# Proto_Recepteur.net
KiCad netlist of a schematic drawn in Altium Designer
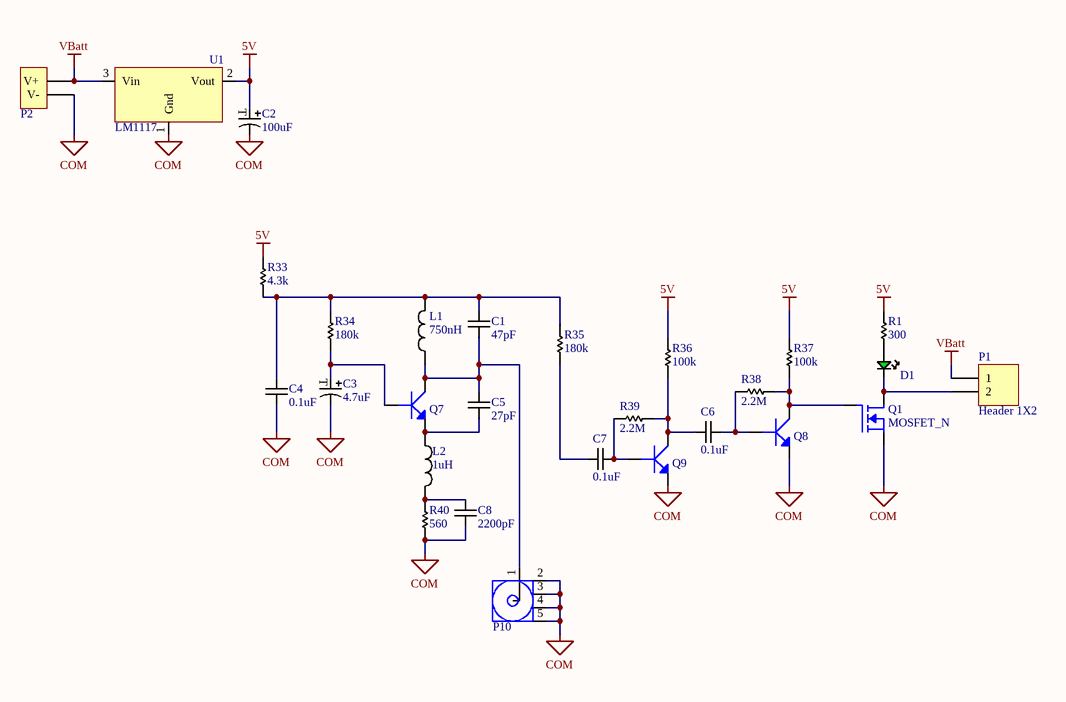
[diagram p0: Proto Recepteur.SchDoc]

(export (version "E")
  (design (tool "Eeschema 10.0.6"))
  (components
    (comp (ref "C1")
      (value "47pF")
      (footprint "0805 - Cap Non-Polarized")
      (description "CAP CER 47PF 100V 5% NP0 0603")
      (fields
        (field (name "PART NUMBER") "Cap-TDK-CGA-47pF-0805")
        (field (name "MANUFACTURER") "TDK")
        (field (name "CREATED BY") "Pier-Yves")
      )
      (libsource (lib "local") (part "Cap"))
    )
    (comp (ref "C2")
      (value "100uF")
      (footprint "Tantalum - Case C")
      (description "CAP TANT 100 16V 10% 2413")
      (fields
        (field (name "PART NUMBER") "Kemet-T491-100uF-16V-1 Ohm")
        (field (name "MANUFACTURER") "Kemet")
        (field (name "CREATED BY") "Frederic")
      )
      (libsource (lib "local") (part "Cap Tantal"))
    )
    (comp (ref "C3")
      (value "4.7uF")
      (footprint "Tantalum - Case D")
      (description "CAP TANT 4.7 35V 10% 2917")
      (fields
        (field (name "PART NUMBER") "Kemet-T491-4.7uF-35V-1.5 Ohm")
        (field (name "MANUFACTURER") "Kemet")
        (field (name "CREATED BY") "Frederic")
      )
      (libsource (lib "local") (part "Cap Tantal"))
    )
    (comp (ref "C4")
      (value "0.1uF")
      (footprint "0805 - Cap Non-Polarized")
      (description "CAP CER 0.1UF 100V 10% X7R 0805")
      (fields
        (field (name "PART NUMBER") "Cap-TDK-CGA-0.1uF-0805")
        (field (name "MANUFACTURER") "TDK")
        (field (name "CREATED BY") "Pier-Yves")
      )
      (libsource (lib "local") (part "Cap"))
    )
    (comp (ref "C5")
      (value "27pF")
      (footprint "0805 - Cap Non-Polarized")
      (description "CAP CER 27PF 50V 5% NP0 0603")
      (fields
        (field (name "PART NUMBER") "Cap-TDK-CGA-27pF-0805")
        (field (name "MANUFACTURER") "TDK")
        (field (name "CREATED BY") "Pier-Yves")
      )
      (libsource (lib "local") (part "Cap"))
    )
    (comp (ref "C6")
      (value "0.1uF")
      (footprint "0805 - Cap Non-Polarized")
      (description "CAP CER 0.1UF 100V 10% X7R 0805")
      (fields
        (field (name "PART NUMBER") "Cap-TDK-CGA-0.1uF-0805")
        (field (name "MANUFACTURER") "TDK")
        (field (name "CREATED BY") "Pier-Yves")
      )
      (libsource (lib "local") (part "Cap"))
    )
    (comp (ref "C7")
      (value "0.1uF")
      (footprint "0805 - Cap Non-Polarized")
      (description "CAP CER 0.1UF 100V 10% X7R 0805")
      (fields
        (field (name "PART NUMBER") "Cap-TDK-CGA-0.1uF-0805")
        (field (name "MANUFACTURER") "TDK")
        (field (name "CREATED BY") "Pier-Yves")
      )
      (libsource (lib "local") (part "Cap"))
    )
    (comp (ref "C8")
      (value "2200pF")
      (footprint "0805 - Cap Non-Polarized")
      (description "CAP CER 2200PF 100V 5% NP0 0805")
      (fields
        (field (name "PART NUMBER") "Cap-TDK-CGA-2200pF-0805")
        (field (name "MANUFACTURER") "TDK")
        (field (name "CREATED BY") "Pier-Yves")
      )
      (libsource (lib "local") (part "Cap"))
    )
    (comp (ref "D1")
      (value "Green")
      (footprint "0805 - Led Green")
      (description "Led Green 0805 Low Brightness - 10mA")
      (fields
        (field (name "PART NUMBER") "LED-Green-lowBrigthness-0805")
        (field (name "MANUFACTURER") "Lite-On inc.")
        (field (name "CREATED BY") "Pier-Yves")
      )
      (libsource (lib "local") (part "Led Green"))
    )
    (comp (ref "L1")
      (value "750nH")
      (footprint "1008 - INDUCTOR")
      (description "IND 750NH 360MA SRF 360MHZ 1008")
      (fields
        (field (name "PART NUMBER") "Murata-LQW2UA-Ind-AirCore-750nH")
        (field (name "MANUFACTURER") "Murata Electronics North America")
        (field (name "CREATED BY") "Frederic")
      )
      (libsource (lib "local") (part "Inductor"))
    )
    (comp (ref "L2")
      (value "1uH")
      (footprint "1008 - INDUCTOR")
      (description "IND 1000NH 370MA SRF 290MHZ 1008")
      (fields
        (field (name "PART NUMBER") "Murata-LQW2UA-Ind-AirCore-1uH")
        (field (name "MANUFACTURER") "Murata Electronics North America")
        (field (name "CREATED BY") "Frederic")
      )
      (libsource (lib "local") (part "Inductor"))
    )
    (comp (ref "P1")
      (value "Header 1X2")
      (footprint "Headers - 1x2 - R/A - Lock")
      (fields
        (field (name "PART NUMBER") "Header-0.100-R/A-Lock-1X2")
        (field (name "MANUFACTURER") "Molex Inc.")
        (field (name "PUBLISHER") "Altium Limited")
        (field (name "CREATED BY") "Pier-Yves")
      )
      (libsource (lib "local") (part "Header 1X2"))
    )
    (comp (ref "P2")
      (value "Battery Holder")
      (footprint "Battery Holder - 9V - THT")
      (description "HOLDER BATTERY 9V PC MOUNT")
      (fields
        (field (name "PART NUMBER") "Battery Holder-9V-THT-Open")
        (field (name "MANUFACTURER") "MPD")
        (field (name "CREATED BY") "Pier-Yves")
      )
      (libsource (lib "local") (part "Battery Holder - 2 pin"))
    )
    (comp (ref "P10")
      (value "Coax-F")
      (footprint "SMA-Female-R/A-THT")
      (description "CONN SMA JACK R/A 50 OHM PCB")
      (fields
        (field (name "PART NUMBER") "coax-sma-ra-tht")
        (field (name "MANUFACTURER") "Linx Technologies Inc.")
        (field (name "CREATED BY") "Pier-Yves")
      )
      (libsource (lib "local") (part "COAX-F"))
    )
    (comp (ref "Q1")
      (value "MOSFET_N")
      (footprint "SOT23-3")
      (description "MosFET Channel-N SOT-23-3 3.3A")
      (fields
        (field (name "PART NUMBER") "2N7002")
        (field (name "MANUFACTURER") "Vishay Siliconix")
        (field (name "CREATED BY") "Pier-Yves")
      )
      (libsource (lib "local") (part "MOSFET_N_GSD"))
    )
    (comp (ref "Q7")
      (value "NPN")
      (footprint "SOT23-3")
      (description "TRANS NPN 40V 350MW SMD SOT23-3")
      (fields
        (field (name "PART NUMBER") "MMBT2222A-7-F")
        (field (name "MANUFACTURER") "Diodes Inc.")
        (field (name "CREATED BY") "Pier-Yves")
      )
      (libsource (lib "local") (part "BJT_NPN_BEC"))
    )
    (comp (ref "Q8")
      (value "NPN")
      (footprint "SOT23-3")
      (description "TRANS NPN 40V 350MW SMD SOT23-3")
      (fields
        (field (name "PART NUMBER") "MMBT2222A-7-F")
        (field (name "MANUFACTURER") "Diodes Inc.")
        (field (name "CREATED BY") "Pier-Yves")
      )
      (libsource (lib "local") (part "BJT_NPN_BEC"))
    )
    (comp (ref "Q9")
      (value "NPN")
      (footprint "SOT23-3")
      (description "TRANS NPN 40V 350MW SMD SOT23-3")
      (fields
        (field (name "PART NUMBER") "MMBT2222A-7-F")
        (field (name "MANUFACTURER") "Diodes Inc.")
        (field (name "CREATED BY") "Pier-Yves")
      )
      (libsource (lib "local") (part "BJT_NPN_BEC"))
    )
    (comp (ref "R1")
      (value "300")
      (footprint "0805 - Resistor")
      (description "RES 300 OHM 1/8W 5% 0805 SMD")
      (fields
        (field (name "PART NUMBER") "Yagao-RC0805-300")
        (field (name "MANUFACTURER") "Yagao")
        (field (name "CREATED BY") "Pier-Yves")
      )
      (libsource (lib "local") (part "Res"))
    )
    (comp (ref "R33")
      (value "4.3k")
      (footprint "0805 - Resistor")
      (description "RES 4.3K OHM 1/8W 5% 0805 SMD")
      (fields
        (field (name "PART NUMBER") "Yagao-RC0805-4.3k")
        (field (name "MANUFACTURER") "Yagao")
        (field (name "CREATED BY") "Pier-Yves")
      )
      (libsource (lib "local") (part "Res"))
    )
    (comp (ref "R34")
      (value "180k")
      (footprint "0805 - Resistor")
      (description "RES 180K OHM 1/8W 5% 0805 SMD")
      (fields
        (field (name "PART NUMBER") "Yagao-RC0805-180k")
        (field (name "MANUFACTURER") "Yagao")
        (field (name "CREATED BY") "Pier-Yves")
      )
      (libsource (lib "local") (part "Res"))
    )
    (comp (ref "R35")
      (value "180k")
      (footprint "0805 - Resistor")
      (description "RES 180K OHM 1/8W 5% 0805 SMD")
      (fields
        (field (name "PART NUMBER") "Yagao-RC0805-180k")
        (field (name "MANUFACTURER") "Yagao")
        (field (name "CREATED BY") "Pier-Yves")
      )
      (libsource (lib "local") (part "Res"))
    )
    (comp (ref "R36")
      (value "100k")
      (footprint "0805 - Resistor")
      (description "RES 100K OHM 1/8W 5% 0805 SMD")
      (fields
        (field (name "PART NUMBER") "Yagao-RC0805-100k")
        (field (name "MANUFACTURER") "Yagao")
        (field (name "CREATED BY") "Pier-Yves")
      )
      (libsource (lib "local") (part "Res"))
    )
    (comp (ref "R37")
      (value "100k")
      (footprint "0805 - Resistor")
      (description "RES 100K OHM 1/8W 5% 0805 SMD")
      (fields
        (field (name "PART NUMBER") "Yagao-RC0805-100k")
        (field (name "MANUFACTURER") "Yagao")
        (field (name "CREATED BY") "Pier-Yves")
      )
      (libsource (lib "local") (part "Res"))
    )
    (comp (ref "R38")
      (value "2.2M")
      (footprint "0805 - Resistor")
      (description "RES 2.2M OHM 1/8W 5% 0805 SMD")
      (fields
        (field (name "PART NUMBER") "Yagao-RC0805-2.2M")
        (field (name "MANUFACTURER") "Yagao")
        (field (name "CREATED BY") "Pier-Yves")
      )
      (libsource (lib "local") (part "Res"))
    )
    (comp (ref "R39")
      (value "2.2M")
      (footprint "0805 - Resistor")
      (description "RES 2.2M OHM 1/8W 5% 0805 SMD")
      (fields
        (field (name "PART NUMBER") "Yagao-RC0805-2.2M")
        (field (name "MANUFACTURER") "Yagao")
        (field (name "CREATED BY") "Pier-Yves")
      )
      (libsource (lib "local") (part "Res"))
    )
    (comp (ref "R40")
      (value "560")
      (footprint "0805 - Resistor")
      (description "RES 560 OHM 1/8W 5% 0805 SMD")
      (fields
        (field (name "PART NUMBER") "Yagao-RC0805-560")
        (field (name "MANUFACTURER") "Yagao")
        (field (name "CREATED BY") "Pier-Yves")
      )
      (libsource (lib "local") (part "Res"))
    )
    (comp (ref "U1")
      (value "LM1117")
      (footprint "SOT223-3")
      (description "Regulator LDO 5V")
      (fields
        (field (name "PART NUMBER") "LM1117 5v SOT223-3")
        (field (name "MANUFACTURER") "Texas Instrument")
        (field (name "CREATED BY") "Pier-Yves")
      )
      (libsource (lib "local") (part "LM1117"))
    )
  )
  (nets
    (net (code "1") (name "5V") (class "Default")
      (node (ref "C2") (pin "1") (pinfunction "1_1") (pintype "passive"))
      (node (ref "R1") (pin "2") (pinfunction "2_2") (pintype "passive"))
      (node (ref "R33") (pin "2") (pinfunction "2_2") (pintype "passive"))
      (node (ref "R36") (pin "1") (pinfunction "1_1") (pintype "passive"))
      (node (ref "R37") (pin "1") (pinfunction "1_1") (pintype "passive"))
      (node (ref "U1") (pin "2") (pinfunction "Vout_2") (pintype "passive"))
    )
    (net (code "2") (name "COM") (class "Default")
      (node (ref "C2") (pin "2") (pinfunction "2_2") (pintype "passive"))
      (node (ref "C3") (pin "2") (pinfunction "2_2") (pintype "passive"))
      (node (ref "C4") (pin "1") (pinfunction "1_1") (pintype "passive"))
      (node (ref "C8") (pin "1") (pinfunction "1_1") (pintype "passive"))
      (node (ref "P10") (pin "2") (pinfunction "GND_2") (pintype "passive"))
      (node (ref "P10") (pin "3") (pinfunction "GND_3") (pintype "passive"))
      (node (ref "P10") (pin "4") (pinfunction "GND_4") (pintype "passive"))
      (node (ref "P10") (pin "5") (pinfunction "GND_5") (pintype "passive"))
      (node (ref "P2") (pin "2") (pinfunction "V-_2") (pintype "passive"))
      (node (ref "Q1") (pin "2") (pinfunction "S_2") (pintype "passive"))
      (node (ref "Q8") (pin "2") (pinfunction "E_2") (pintype "passive"))
      (node (ref "Q9") (pin "2") (pinfunction "E_2") (pintype "passive"))
      (node (ref "R40") (pin "1") (pinfunction "1_1") (pintype "passive"))
      (node (ref "U1") (pin "1") (pinfunction "Gnd_1") (pintype "passive"))
    )
    (net (code "3") (name "Net-(C1-Pad2)") (class "Default")
      (node (ref "C1") (pin "2") (pinfunction "2_2") (pintype "passive"))
      (node (ref "C4") (pin "2") (pinfunction "2_2") (pintype "passive"))
      (node (ref "L1") (pin "2") (pinfunction "2_2") (pintype "passive"))
      (node (ref "R33") (pin "1") (pinfunction "1_1") (pintype "passive"))
      (node (ref "R34") (pin "1") (pinfunction "1_1") (pintype "passive"))
      (node (ref "R35") (pin "2") (pinfunction "2_2") (pintype "passive"))
    )
    (net (code "4") (name "Net-(C7-Pad2)") (class "Default")
      (node (ref "C7") (pin "2") (pinfunction "2_2") (pintype "passive"))
      (node (ref "R35") (pin "1") (pinfunction "1_1") (pintype "passive"))
    )
    (net (code "5") (name "Net-(C8-Pad2)") (class "Default")
      (node (ref "C8") (pin "2") (pinfunction "2_2") (pintype "passive"))
      (node (ref "L2") (pin "2") (pinfunction "2_2") (pintype "passive"))
      (node (ref "R40") (pin "2") (pinfunction "2_2") (pintype "passive"))
    )
    (net (code "6") (name "Net-(D1-A)") (class "Default")
      (node (ref "D1") (pin "1") (pinfunction "A_1") (pintype "passive"))
      (node (ref "R1") (pin "1") (pinfunction "1_1") (pintype "passive"))
    )
    (net (code "7") (name "Net-(D1-K)") (class "Default")
      (node (ref "D1") (pin "2") (pinfunction "K_2") (pintype "passive"))
      (node (ref "P1") (pin "2") (pinfunction "2_2") (pintype "passive"))
      (node (ref "Q1") (pin "3") (pinfunction "D_3") (pintype "passive"))
    )
    (net (code "8") (name "Net-(P10-Signal)") (class "Default")
      (node (ref "C1") (pin "1") (pinfunction "1_1") (pintype "passive"))
      (node (ref "C5") (pin "2") (pinfunction "2_2") (pintype "passive"))
      (node (ref "L1") (pin "1") (pinfunction "1_1") (pintype "passive"))
      (node (ref "P10") (pin "1") (pinfunction "Signal_1") (pintype "passive"))
      (node (ref "Q7") (pin "3") (pinfunction "C_3") (pintype "passive"))
    )
    (net (code "9") (name "Net-(Q1-G)") (class "Default")
      (node (ref "Q1") (pin "1") (pinfunction "G_1") (pintype "passive"))
      (node (ref "Q8") (pin "3") (pinfunction "C_3") (pintype "passive"))
      (node (ref "R37") (pin "2") (pinfunction "2_2") (pintype "passive"))
      (node (ref "R38") (pin "2") (pinfunction "2_2") (pintype "passive"))
    )
    (net (code "10") (name "Net-(Q7-B)") (class "Default")
      (node (ref "C3") (pin "1") (pinfunction "1_1") (pintype "passive"))
      (node (ref "Q7") (pin "1") (pinfunction "B_1") (pintype "passive"))
      (node (ref "R34") (pin "2") (pinfunction "2_2") (pintype "passive"))
    )
    (net (code "11") (name "Net-(Q7-E)") (class "Default")
      (node (ref "C5") (pin "1") (pinfunction "1_1") (pintype "passive"))
      (node (ref "L2") (pin "1") (pinfunction "1_1") (pintype "passive"))
      (node (ref "Q7") (pin "2") (pinfunction "E_2") (pintype "passive"))
    )
    (net (code "12") (name "Net-(Q8-B)") (class "Default")
      (node (ref "C6") (pin "1") (pinfunction "1_1") (pintype "passive"))
      (node (ref "Q8") (pin "1") (pinfunction "B_1") (pintype "passive"))
      (node (ref "R38") (pin "1") (pinfunction "1_1") (pintype "passive"))
    )
    (net (code "13") (name "Net-(Q9-B)") (class "Default")
      (node (ref "C7") (pin "1") (pinfunction "1_1") (pintype "passive"))
      (node (ref "Q9") (pin "1") (pinfunction "B_1") (pintype "passive"))
      (node (ref "R39") (pin "1") (pinfunction "1_1") (pintype "passive"))
    )
    (net (code "14") (name "Net-(Q9-C)") (class "Default")
      (node (ref "C6") (pin "2") (pinfunction "2_2") (pintype "passive"))
      (node (ref "Q9") (pin "3") (pinfunction "C_3") (pintype "passive"))
      (node (ref "R36") (pin "2") (pinfunction "2_2") (pintype "passive"))
      (node (ref "R39") (pin "2") (pinfunction "2_2") (pintype "passive"))
    )
    (net (code "15") (name "VBatt") (class "Default")
      (node (ref "P1") (pin "1") (pinfunction "1_1") (pintype "passive"))
      (node (ref "P2") (pin "1") (pinfunction "V+_1") (pintype "passive"))
      (node (ref "U1") (pin "3") (pinfunction "Vin_3") (pintype "passive"))
    )
  )
)
